# IO.net
KiCad netlist of a schematic drawn in Altium Designer
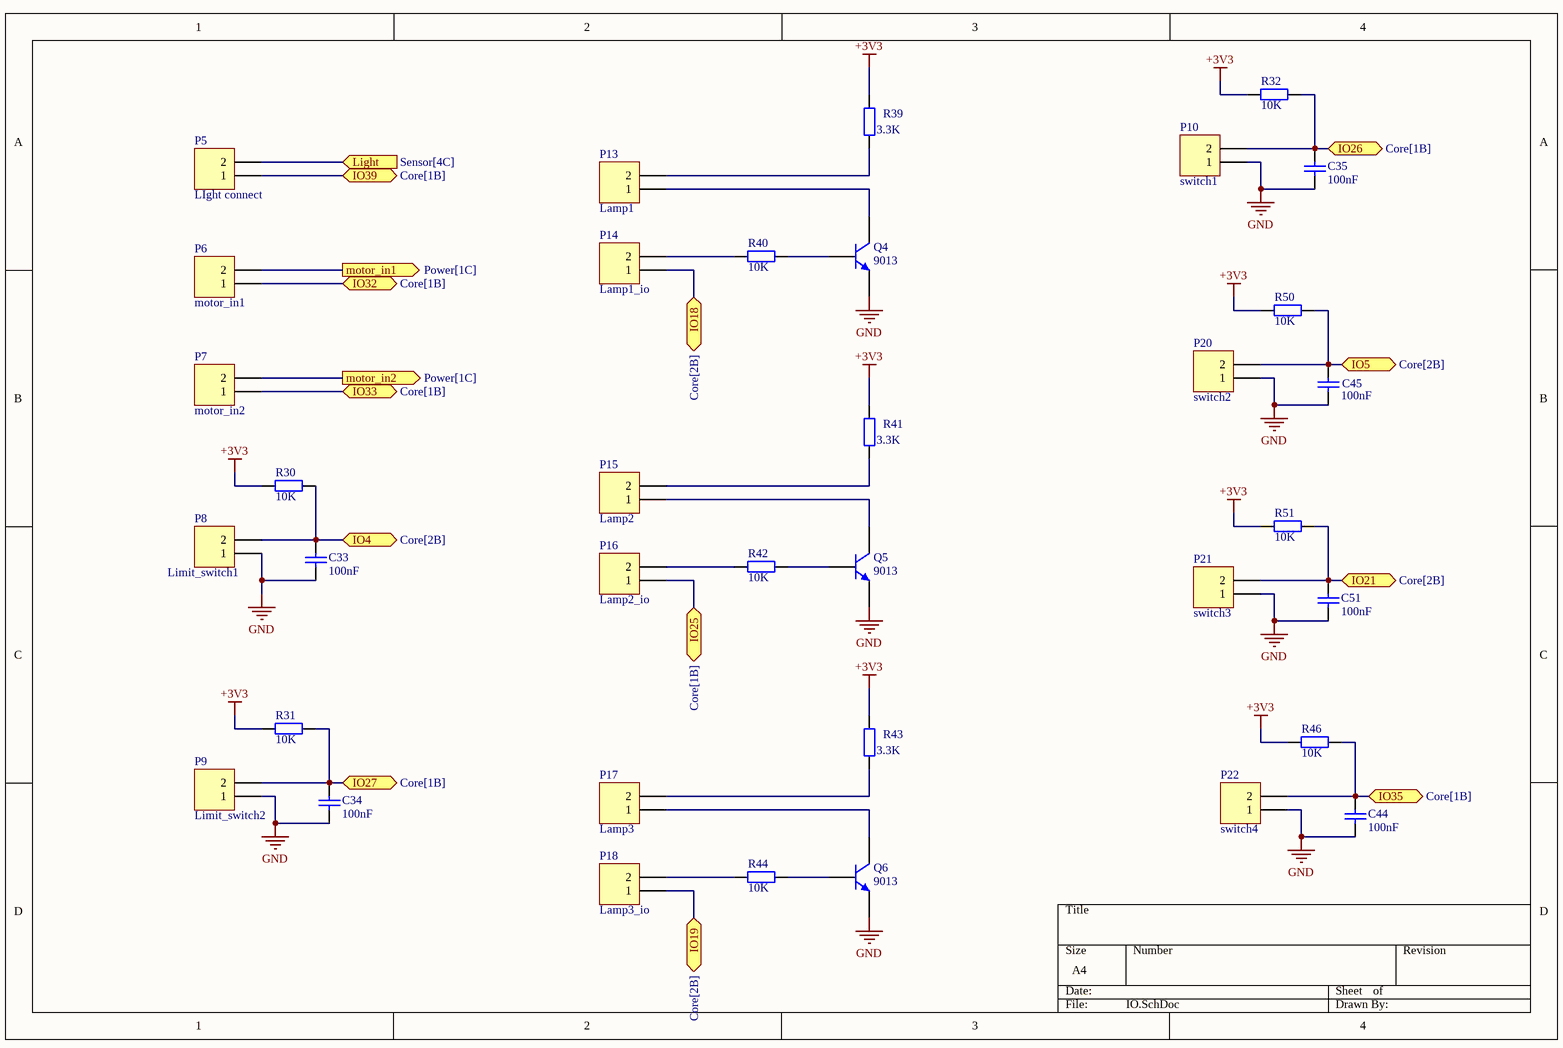
[diagram p0: IO.SchDoc]

(export (version "E")
  (design (tool "Eeschema 10.0.6"))
  (components
    (comp (ref "C33")
      (value "100nF")
      (footprint "6-0805_N")
      (description "Capacitor")
      (fields (field (name "Comment") "Cap") (field (name "PUBLISHER") "Altium Limited"))
      (libsource (lib "Miscellaneous Devices") (part "Cap"))
    )
    (comp (ref "C34")
      (value "100nF")
      (footprint "6-0805_N")
      (description "Capacitor")
      (fields (field (name "Comment") "Cap") (field (name "PUBLISHER") "Altium Limited"))
      (libsource (lib "Miscellaneous Devices") (part "Cap"))
    )
    (comp (ref "C35")
      (value "100nF")
      (footprint "6-0805_N")
      (description "Capacitor")
      (fields (field (name "Comment") "Cap") (field (name "PUBLISHER") "Altium Limited"))
      (libsource (lib "Miscellaneous Devices") (part "Cap"))
    )
    (comp (ref "C44")
      (value "100nF")
      (footprint "6-0805_N")
      (description "Capacitor")
      (fields (field (name "Comment") "Cap") (field (name "PUBLISHER") "Altium Limited"))
      (libsource (lib "Miscellaneous Devices") (part "Cap"))
    )
    (comp (ref "C45")
      (value "100nF")
      (footprint "6-0805_N")
      (description "Capacitor")
      (fields (field (name "Comment") "Cap") (field (name "PUBLISHER") "Altium Limited"))
      (libsource (lib "Miscellaneous Devices") (part "Cap"))
    )
    (comp (ref "C51")
      (value "100nF")
      (footprint "6-0805_N")
      (description "Capacitor")
      (fields (field (name "Comment") "Cap") (field (name "PUBLISHER") "Altium Limited"))
      (libsource (lib "Miscellaneous Devices") (part "Cap"))
    )
    (comp (ref "P5")
      (value "LIght connect")
      (footprint "HDR1X2")
      (description "Header, 2-Pin")
      (fields (field (name "PUBLISHER") "Altium Limited"))
      (libsource (lib "Miscellaneous Connectors") (part "Header 2"))
    )
    (comp (ref "P6")
      (value "motor_in1")
      (footprint "HDR1X2")
      (description "Header, 2-Pin")
      (fields (field (name "PUBLISHER") "Altium Limited"))
      (libsource (lib "Miscellaneous Connectors") (part "Header 2"))
    )
    (comp (ref "P7")
      (value "motor_in2")
      (footprint "HDR1X2")
      (description "Header, 2-Pin")
      (fields (field (name "PUBLISHER") "Altium Limited"))
      (libsource (lib "Miscellaneous Connectors") (part "Header 2"))
    )
    (comp (ref "P8")
      (value "Limit_switch1")
      (footprint "HDR1X2")
      (description "Header, 2-Pin")
      (fields (field (name "PUBLISHER") "Altium Limited"))
      (libsource (lib "Miscellaneous Connectors") (part "Header 2"))
    )
    (comp (ref "P9")
      (value "Limit_switch2")
      (footprint "HDR1X2")
      (description "Header, 2-Pin")
      (fields (field (name "PUBLISHER") "Altium Limited"))
      (libsource (lib "Miscellaneous Connectors") (part "Header 2"))
    )
    (comp (ref "P10")
      (value "switch1")
      (footprint "HDR1X2")
      (description "Header, 2-Pin")
      (fields (field (name "PUBLISHER") "Altium Limited"))
      (libsource (lib "Miscellaneous Connectors") (part "Header 2"))
    )
    (comp (ref "P13")
      (value "Lamp1")
      (footprint "HDR1X2")
      (description "Header, 2-Pin")
      (fields (field (name "PUBLISHER") "Altium Limited"))
      (libsource (lib "Miscellaneous Connectors") (part "Header 2"))
    )
    (comp (ref "P14")
      (value "Lamp1_io")
      (footprint "HDR1X2")
      (description "Header, 2-Pin")
      (fields (field (name "PUBLISHER") "Altium Limited"))
      (libsource (lib "Miscellaneous Connectors") (part "Header 2"))
    )
    (comp (ref "P15")
      (value "Lamp2")
      (footprint "HDR1X2")
      (description "Header, 2-Pin")
      (fields (field (name "PUBLISHER") "Altium Limited"))
      (libsource (lib "Miscellaneous Connectors") (part "Header 2"))
    )
    (comp (ref "P16")
      (value "Lamp2_io")
      (footprint "HDR1X2")
      (description "Header, 2-Pin")
      (fields (field (name "PUBLISHER") "Altium Limited"))
      (libsource (lib "Miscellaneous Connectors") (part "Header 2"))
    )
    (comp (ref "P17")
      (value "Lamp3")
      (footprint "HDR1X2")
      (description "Header, 2-Pin")
      (fields (field (name "PUBLISHER") "Altium Limited"))
      (libsource (lib "Miscellaneous Connectors") (part "Header 2"))
    )
    (comp (ref "P18")
      (value "Lamp3_io")
      (footprint "HDR1X2")
      (description "Header, 2-Pin")
      (fields (field (name "PUBLISHER") "Altium Limited"))
      (libsource (lib "Miscellaneous Connectors") (part "Header 2"))
    )
    (comp (ref "P20")
      (value "switch2")
      (footprint "HDR1X2")
      (description "Header, 2-Pin")
      (fields (field (name "PUBLISHER") "Altium Limited"))
      (libsource (lib "Miscellaneous Connectors") (part "Header 2"))
    )
    (comp (ref "P21")
      (value "switch3")
      (footprint "HDR1X2")
      (description "Header, 2-Pin")
      (fields (field (name "PUBLISHER") "Altium Limited"))
      (libsource (lib "Miscellaneous Connectors") (part "Header 2"))
    )
    (comp (ref "P22")
      (value "switch4")
      (footprint "HDR1X2")
      (description "Header, 2-Pin")
      (fields (field (name "PUBLISHER") "Altium Limited"))
      (libsource (lib "Miscellaneous Connectors") (part "Header 2"))
    )
    (comp (ref "Q4")
      (value "9013")
      (footprint "SOT-23-3_L2.9-W1.3-P1.90-LS2.4-BR")
      (description "NPN General Purpose Amplifier")
      (fields (field (name "PUBLISHER") "Altium Limited"))
      (libsource (lib "Miscellaneous Devices") (part "2N3904"))
    )
    (comp (ref "Q5")
      (value "9013")
      (footprint "SOT-23-3_L2.9-W1.3-P1.90-LS2.4-BR")
      (description "NPN General Purpose Amplifier")
      (fields (field (name "PUBLISHER") "Altium Limited"))
      (libsource (lib "Miscellaneous Devices") (part "2N3904"))
    )
    (comp (ref "Q6")
      (value "9013")
      (footprint "SOT-23-3_L2.9-W1.3-P1.90-LS2.4-BR")
      (description "NPN General Purpose Amplifier")
      (fields (field (name "PUBLISHER") "Altium Limited"))
      (libsource (lib "Miscellaneous Devices") (part "2N3904"))
    )
    (comp (ref "R30")
      (value "10K")
      (footprint "6-0805_N")
      (description "Resistor")
      (fields (field (name "Comment") "Res2") (field (name "PUBLISHER") "Altium Limited"))
      (libsource (lib "Miscellaneous Devices") (part "Res2"))
    )
    (comp (ref "R31")
      (value "10K")
      (footprint "6-0805_N")
      (description "Resistor")
      (fields (field (name "Comment") "Res2") (field (name "PUBLISHER") "Altium Limited"))
      (libsource (lib "Miscellaneous Devices") (part "Res2"))
    )
    (comp (ref "R32")
      (value "10K")
      (footprint "6-0805_N")
      (description "Resistor")
      (fields (field (name "Comment") "Res2") (field (name "PUBLISHER") "Altium Limited"))
      (libsource (lib "Miscellaneous Devices") (part "Res2"))
    )
    (comp (ref "R39")
      (value "3.3K")
      (footprint "6-0805_N")
      (description "Resistor")
      (fields (field (name "Comment") "Res2") (field (name "PUBLISHER") "Altium Limited"))
      (libsource (lib "") (part "Res2_1"))
    )
    (comp (ref "R40")
      (value "10K")
      (footprint "6-0805_N")
      (description "Resistor")
      (fields (field (name "Comment") "Res2") (field (name "PUBLISHER") "Altium Limited"))
      (libsource (lib "Miscellaneous Devices") (part "Res2"))
    )
    (comp (ref "R41")
      (value "3.3K")
      (footprint "6-0805_N")
      (description "Resistor")
      (fields (field (name "Comment") "Res2") (field (name "PUBLISHER") "Altium Limited"))
      (libsource (lib "") (part "Res2_1"))
    )
    (comp (ref "R42")
      (value "10K")
      (footprint "6-0805_N")
      (description "Resistor")
      (fields (field (name "Comment") "Res2") (field (name "PUBLISHER") "Altium Limited"))
      (libsource (lib "Miscellaneous Devices") (part "Res2"))
    )
    (comp (ref "R43")
      (value "3.3K")
      (footprint "6-0805_N")
      (description "Resistor")
      (fields (field (name "Comment") "Res2") (field (name "PUBLISHER") "Altium Limited"))
      (libsource (lib "") (part "Res2_1"))
    )
    (comp (ref "R44")
      (value "10K")
      (footprint "6-0805_N")
      (description "Resistor")
      (fields (field (name "Comment") "Res2") (field (name "PUBLISHER") "Altium Limited"))
      (libsource (lib "Miscellaneous Devices") (part "Res2"))
    )
    (comp (ref "R46")
      (value "10K")
      (footprint "6-0805_N")
      (description "Resistor")
      (fields (field (name "Comment") "Res2") (field (name "PUBLISHER") "Altium Limited"))
      (libsource (lib "Miscellaneous Devices") (part "Res2"))
    )
    (comp (ref "R50")
      (value "10K")
      (footprint "6-0805_N")
      (description "Resistor")
      (fields (field (name "Comment") "Res2") (field (name "PUBLISHER") "Altium Limited"))
      (libsource (lib "Miscellaneous Devices") (part "Res2"))
    )
    (comp (ref "R51")
      (value "10K")
      (footprint "6-0805_N")
      (description "Resistor")
      (fields (field (name "Comment") "Res2") (field (name "PUBLISHER") "Altium Limited"))
      (libsource (lib "Miscellaneous Devices") (part "Res2"))
    )
  )
  (nets
    (net (code "1") (name "+3V3") (class "Default")
      (node (ref "R30") (pin "1") (pinfunction "1_1") (pintype "passive"))
      (node (ref "R31") (pin "1") (pinfunction "1_1") (pintype "passive"))
      (node (ref "R32") (pin "1") (pinfunction "1_1") (pintype "passive"))
      (node (ref "R39") (pin "1") (pinfunction "1_1") (pintype "passive"))
      (node (ref "R41") (pin "1") (pinfunction "1_1") (pintype "passive"))
      (node (ref "R43") (pin "1") (pinfunction "1_1") (pintype "passive"))
      (node (ref "R46") (pin "1") (pinfunction "1_1") (pintype "passive"))
      (node (ref "R50") (pin "1") (pinfunction "1_1") (pintype "passive"))
      (node (ref "R51") (pin "1") (pinfunction "1_1") (pintype "passive"))
    )
    (net (code "2") (name "/IO4") (class "Default")
      (node (ref "C33") (pin "2") (pinfunction "2_2") (pintype "passive"))
      (node (ref "P8") (pin "2") (pinfunction "2_2") (pintype "passive"))
      (node (ref "R30") (pin "2") (pinfunction "2_2") (pintype "passive"))
    )
    (net (code "3") (name "/IO5") (class "Default")
      (node (ref "C45") (pin "2") (pinfunction "2_2") (pintype "passive"))
      (node (ref "P20") (pin "2") (pinfunction "2_2") (pintype "passive"))
      (node (ref "R50") (pin "2") (pinfunction "2_2") (pintype "passive"))
    )
    (net (code "4") (name "/IO18") (class "Default")
      (node (ref "P14") (pin "1") (pinfunction "1_1") (pintype "passive"))
    )
    (net (code "5") (name "/IO19") (class "Default")
      (node (ref "P18") (pin "1") (pinfunction "1_1") (pintype "passive"))
    )
    (net (code "6") (name "/IO21") (class "Default")
      (node (ref "C51") (pin "2") (pinfunction "2_2") (pintype "passive"))
      (node (ref "P21") (pin "2") (pinfunction "2_2") (pintype "passive"))
      (node (ref "R51") (pin "2") (pinfunction "2_2") (pintype "passive"))
    )
    (net (code "7") (name "/IO25") (class "Default")
      (node (ref "P16") (pin "1") (pinfunction "1_1") (pintype "passive"))
    )
    (net (code "8") (name "/IO26") (class "Default")
      (node (ref "C35") (pin "2") (pinfunction "2_2") (pintype "passive"))
      (node (ref "P10") (pin "2") (pinfunction "2_2") (pintype "passive"))
      (node (ref "R32") (pin "2") (pinfunction "2_2") (pintype "passive"))
    )
    (net (code "9") (name "/IO27") (class "Default")
      (node (ref "C34") (pin "2") (pinfunction "2_2") (pintype "passive"))
      (node (ref "P9") (pin "2") (pinfunction "2_2") (pintype "passive"))
      (node (ref "R31") (pin "2") (pinfunction "2_2") (pintype "passive"))
    )
    (net (code "10") (name "/IO32") (class "Default")
      (node (ref "P6") (pin "1") (pinfunction "1_1") (pintype "passive"))
    )
    (net (code "11") (name "/IO33") (class "Default")
      (node (ref "P7") (pin "1") (pinfunction "1_1") (pintype "passive"))
    )
    (net (code "12") (name "/IO35") (class "Default")
      (node (ref "C44") (pin "2") (pinfunction "2_2") (pintype "passive"))
      (node (ref "P22") (pin "2") (pinfunction "2_2") (pintype "passive"))
      (node (ref "R46") (pin "2") (pinfunction "2_2") (pintype "passive"))
    )
    (net (code "13") (name "/IO39") (class "Default")
      (node (ref "P5") (pin "1") (pinfunction "1_1") (pintype "passive"))
    )
    (net (code "14") (name "/Light") (class "Default")
      (node (ref "P5") (pin "2") (pinfunction "2_2") (pintype "passive"))
    )
    (net (code "15") (name "/motor_in1") (class "Default")
      (node (ref "P6") (pin "2") (pinfunction "2_2") (pintype "passive"))
    )
    (net (code "16") (name "/motor_in2") (class "Default")
      (node (ref "P7") (pin "2") (pinfunction "2_2") (pintype "passive"))
    )
    (net (code "17") (name "GND") (class "Default")
      (node (ref "C33") (pin "1") (pinfunction "1_1") (pintype "passive"))
      (node (ref "C34") (pin "1") (pinfunction "1_1") (pintype "passive"))
      (node (ref "C35") (pin "1") (pinfunction "1_1") (pintype "passive"))
      (node (ref "C44") (pin "1") (pinfunction "1_1") (pintype "passive"))
      (node (ref "C45") (pin "1") (pinfunction "1_1") (pintype "passive"))
      (node (ref "C51") (pin "1") (pinfunction "1_1") (pintype "passive"))
      (node (ref "P10") (pin "1") (pinfunction "1_1") (pintype "passive"))
      (node (ref "P20") (pin "1") (pinfunction "1_1") (pintype "passive"))
      (node (ref "P21") (pin "1") (pinfunction "1_1") (pintype "passive"))
      (node (ref "P22") (pin "1") (pinfunction "1_1") (pintype "passive"))
      (node (ref "P8") (pin "1") (pinfunction "1_1") (pintype "passive"))
      (node (ref "P9") (pin "1") (pinfunction "1_1") (pintype "passive"))
      (node (ref "Q4") (pin "1") (pinfunction "E_1") (pintype "passive"))
      (node (ref "Q5") (pin "1") (pinfunction "E_1") (pintype "passive"))
      (node (ref "Q6") (pin "1") (pinfunction "E_1") (pintype "passive"))
    )
    (net (code "18") (name "Net-(P13-Pad2)") (class "Default")
      (node (ref "P13") (pin "2") (pinfunction "2_2") (pintype "passive"))
      (node (ref "R39") (pin "2") (pinfunction "2_2") (pintype "passive"))
    )
    (net (code "19") (name "Net-(P14-Pad2)") (class "Default")
      (node (ref "P14") (pin "2") (pinfunction "2_2") (pintype "passive"))
      (node (ref "R40") (pin "1") (pinfunction "1_1") (pintype "passive"))
    )
    (net (code "20") (name "Net-(P15-Pad2)") (class "Default")
      (node (ref "P15") (pin "2") (pinfunction "2_2") (pintype "passive"))
      (node (ref "R41") (pin "2") (pinfunction "2_2") (pintype "passive"))
    )
    (net (code "21") (name "Net-(P16-Pad2)") (class "Default")
      (node (ref "P16") (pin "2") (pinfunction "2_2") (pintype "passive"))
      (node (ref "R42") (pin "1") (pinfunction "1_1") (pintype "passive"))
    )
    (net (code "22") (name "Net-(P17-Pad2)") (class "Default")
      (node (ref "P17") (pin "2") (pinfunction "2_2") (pintype "passive"))
      (node (ref "R43") (pin "2") (pinfunction "2_2") (pintype "passive"))
    )
    (net (code "23") (name "Net-(P18-Pad2)") (class "Default")
      (node (ref "P18") (pin "2") (pinfunction "2_2") (pintype "passive"))
      (node (ref "R44") (pin "1") (pinfunction "1_1") (pintype "passive"))
    )
    (net (code "24") (name "Net-(Q4-B)") (class "Default")
      (node (ref "Q4") (pin "2") (pinfunction "B_2") (pintype "passive"))
      (node (ref "R40") (pin "2") (pinfunction "2_2") (pintype "passive"))
    )
    (net (code "25") (name "Net-(Q4-C)") (class "Default")
      (node (ref "P13") (pin "1") (pinfunction "1_1") (pintype "passive"))
      (node (ref "Q4") (pin "3") (pinfunction "C_3") (pintype "passive"))
    )
    (net (code "26") (name "Net-(Q5-B)") (class "Default")
      (node (ref "Q5") (pin "2") (pinfunction "B_2") (pintype "passive"))
      (node (ref "R42") (pin "2") (pinfunction "2_2") (pintype "passive"))
    )
    (net (code "27") (name "Net-(Q5-C)") (class "Default")
      (node (ref "P15") (pin "1") (pinfunction "1_1") (pintype "passive"))
      (node (ref "Q5") (pin "3") (pinfunction "C_3") (pintype "passive"))
    )
    (net (code "28") (name "Net-(Q6-B)") (class "Default")
      (node (ref "Q6") (pin "2") (pinfunction "B_2") (pintype "passive"))
      (node (ref "R44") (pin "2") (pinfunction "2_2") (pintype "passive"))
    )
    (net (code "29") (name "Net-(Q6-C)") (class "Default")
      (node (ref "P17") (pin "1") (pinfunction "1_1") (pintype "passive"))
      (node (ref "Q6") (pin "3") (pinfunction "C_3") (pintype "passive"))
    )
  )
)
